# Rev_B.net
KiCad netlist of a schematic drawn in EAGLE
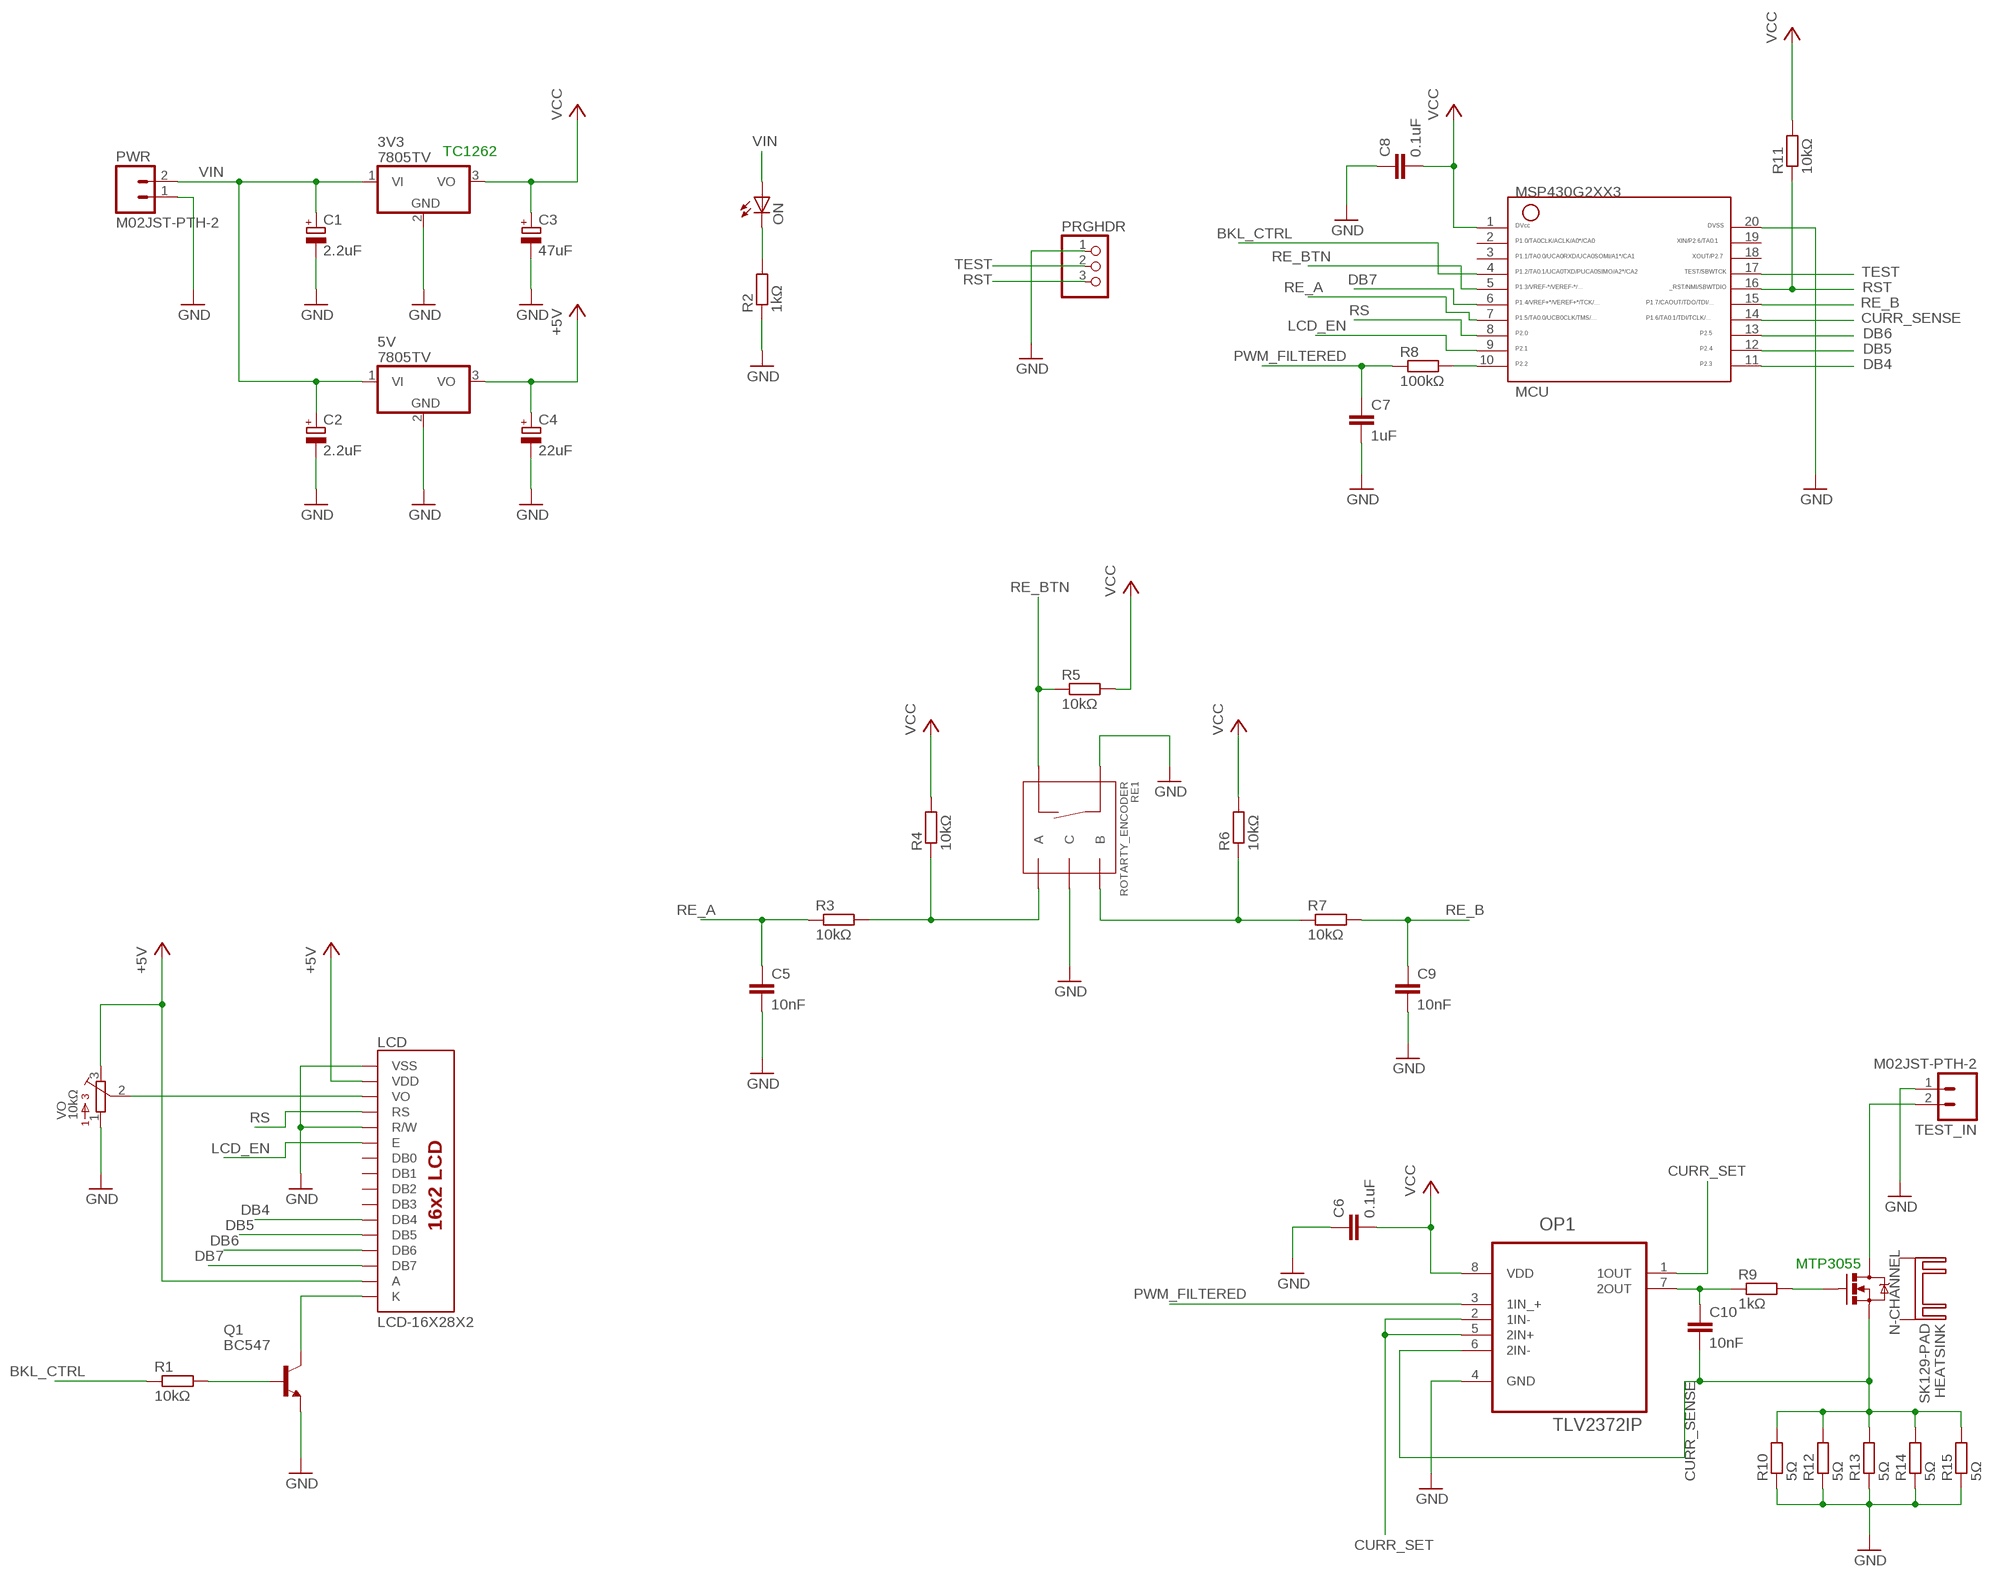
[diagram p0: schematic, sheet 1]

(export (version "E")
  (design (tool "Eeschema 10.0.6"))
  (components
    (comp (ref "3V3")
      (value "7805TV")
      (footprint "eagle-import:TO220V")
      (libsource (lib "eagle-import") (part "78TV05"))
    )
    (comp (ref "5V")
      (value "7805TV")
      (footprint "eagle-import:TO220V")
      (libsource (lib "eagle-import") (part "78TV05"))
    )
    (comp (ref "C1")
      (value "2.2uF")
      (footprint "eagle-import:E2,5-6")
      (libsource (lib "eagle-import") (part "CPOL-EUE2.5-6"))
    )
    (comp (ref "C2")
      (value "2.2uF")
      (footprint "eagle-import:E2,5-6")
      (libsource (lib "eagle-import") (part "CPOL-EUE2.5-6"))
    )
    (comp (ref "C3")
      (value "47uF")
      (footprint "eagle-import:E2,5-6")
      (libsource (lib "eagle-import") (part "CPOL-EUE2.5-6"))
    )
    (comp (ref "C4")
      (value "22uF")
      (footprint "eagle-import:E2,5-6")
      (libsource (lib "eagle-import") (part "CPOL-EUE2.5-6"))
    )
    (comp (ref "C5")
      (value "10nF")
      (footprint "eagle-import:C050-025X075")
      (libsource (lib "eagle-import") (part "C-EU050-025X075"))
    )
    (comp (ref "C6")
      (value "0.1uF")
      (footprint "eagle-import:C050-025X075")
      (libsource (lib "eagle-import") (part "C-EU050-025X075"))
    )
    (comp (ref "C7")
      (value "1uF")
      (footprint "eagle-import:C025-025X050")
      (libsource (lib "eagle-import") (part "C-EU025-025X050"))
    )
    (comp (ref "C8")
      (value "0.1uF")
      (footprint "eagle-import:C050-025X075")
      (libsource (lib "eagle-import") (part "C-EU050-025X075"))
    )
    (comp (ref "C9")
      (value "10nF")
      (footprint "eagle-import:C050-025X075")
      (libsource (lib "eagle-import") (part "C-EU050-025X075"))
    )
    (comp (ref "C10")
      (value "10nF")
      (footprint "eagle-import:C050-025X075")
      (libsource (lib "eagle-import") (part "C-EU050-025X075"))
    )
    (comp (ref "HEATSINK")
      (value "SK129-PAD")
      (footprint "eagle-import:SK129")
      (libsource (lib "eagle-import") (part "SK129-PAD"))
    )
    (comp (ref "LCD")
      (value "LCD-16X28X2")
      (footprint "eagle-import:LCD-8X2")
      (libsource (lib "eagle-import") (part "LCD-16X28X2"))
    )
    (comp (ref "MCU")
      (value "G2XX3---N20")
      (footprint "eagle-import:N20")
      (libsource (lib "eagle-import") (part "G2XX3---N20"))
    )
    (comp (ref "N-CHANNEL")
      (value "MOSFET-NCHANNELFQP30N06L")
      (footprint "eagle-import:TO220V")
      (libsource (lib "eagle-import") (part "MOSFET-NCHANNELFQP30N06L"))
    )
    (comp (ref "ON")
      (value "LEDSQR2X5")
      (footprint "eagle-import:LED2X5")
      (libsource (lib "eagle-import") (part "LEDSQR2X5"))
    )
    (comp (ref "OP1")
      (value "TLV2372IP")
      (footprint "eagle-import:DIP254P762X508-8")
      (libsource (lib "eagle-import") (part "TLV2372IP"))
    )
    (comp (ref "PRGHDR")
      (value "PINHD-1X3")
      (footprint "eagle-import:1X03")
      (libsource (lib "eagle-import") (part "PINHD-1X3"))
    )
    (comp (ref "PWR")
      (value "M02JST-PTH-2")
      (footprint "eagle-import:JST-2-PTH")
      (libsource (lib "eagle-import") (part "M02JST-PTH-2"))
    )
    (comp (ref "Q1")
      (value "BC547")
      (footprint "eagle-import:TO92")
      (libsource (lib "eagle-import") (part "BC547"))
    )
    (comp (ref "R1")
      (value "10kΩ")
      (footprint "eagle-import:0207_10")
      (libsource (lib "eagle-import") (part "resistor_R-EU_0207/10"))
    )
    (comp (ref "R2")
      (value "1kΩ")
      (footprint "eagle-import:0207_10")
      (libsource (lib "eagle-import") (part "resistor_R-EU_0207/10"))
    )
    (comp (ref "R3")
      (value "10kΩ")
      (footprint "eagle-import:0207_10")
      (libsource (lib "eagle-import") (part "resistor_R-EU_0207/10"))
    )
    (comp (ref "R4")
      (value "10kΩ")
      (footprint "eagle-import:0207_10")
      (libsource (lib "eagle-import") (part "resistor_R-EU_0207/10"))
    )
    (comp (ref "R5")
      (value "10kΩ")
      (footprint "eagle-import:0207_10")
      (libsource (lib "eagle-import") (part "resistor_R-EU_0207/10"))
    )
    (comp (ref "R6")
      (value "10kΩ")
      (footprint "eagle-import:0207_10")
      (libsource (lib "eagle-import") (part "resistor_R-EU_0207/10"))
    )
    (comp (ref "R7")
      (value "10kΩ")
      (footprint "eagle-import:0207_10")
      (libsource (lib "eagle-import") (part "resistor_R-EU_0207/10"))
    )
    (comp (ref "R8")
      (value "100kΩ")
      (footprint "eagle-import:0207_10")
      (libsource (lib "eagle-import") (part "resistor_R-EU_0207/10"))
    )
    (comp (ref "R9")
      (value "1kΩ")
      (footprint "eagle-import:0207_10")
      (libsource (lib "eagle-import") (part "resistor_R-EU_0207/10"))
    )
    (comp (ref "R10")
      (value "5Ω")
      (footprint "eagle-import:P0613_15")
      (libsource (lib "eagle-import") (part "R-EU_0613/15"))
    )
    (comp (ref "R11")
      (value "10kΩ")
      (footprint "eagle-import:0207_10")
      (libsource (lib "eagle-import") (part "resistor_R-EU_0207/10"))
    )
    (comp (ref "R12")
      (value "5Ω")
      (footprint "eagle-import:P0613_15")
      (libsource (lib "eagle-import") (part "R-EU_0613/15"))
    )
    (comp (ref "R13")
      (value "5Ω")
      (footprint "eagle-import:P0613_15")
      (libsource (lib "eagle-import") (part "R-EU_0613/15"))
    )
    (comp (ref "R14")
      (value "5Ω")
      (footprint "eagle-import:P0613_15")
      (libsource (lib "eagle-import") (part "R-EU_0613/15"))
    )
    (comp (ref "R15")
      (value "5Ω")
      (footprint "eagle-import:P0613_15")
      (libsource (lib "eagle-import") (part "R-EU_0613/15"))
    )
    (comp (ref "RE1")
      (value "ROTARTY_ENCODER")
      (footprint "eagle-import:ROTARY_ENC_PLAIN")
      (libsource (lib "eagle-import") (part "ROTARTY_ENCODER"))
    )
    (comp (ref "TEST_IN")
      (value "M02JST-PTH-2")
      (footprint "eagle-import:JST-2-PTH")
      (libsource (lib "eagle-import") (part "M02JST-PTH-2"))
    )
    (comp (ref "VO")
      (value "10kΩ")
      (footprint "eagle-import:3362H")
      (libsource (lib "eagle-import") (part "3362H"))
    )
  )
  (nets
    (net (code "1") (name "+5V") (class "Default")
      (node (ref "5V") (pin "3") (pinfunction "VO_3") (pintype "passive"))
      (node (ref "C4") (pin "+") (pinfunction "+_+") (pintype "passive"))
      (node (ref "LCD") (pin "15") (pinfunction "A_15") (pintype "power_in"))
      (node (ref "LCD") (pin "2") (pinfunction "VDD_2") (pintype "power_in"))
      (node (ref "VO") (pin "3") (pinfunction "3_3") (pintype "passive"))
    )
    (net (code "2") (name "/BKL_CTRL") (class "Default")
      (node (ref "MCU") (pin "4") (pinfunction "4_4") (pintype "bidirectional"))
      (node (ref "R1") (pin "1") (pinfunction "1_1") (pintype "passive"))
    )
    (net (code "3") (name "/CURR_SENSE") (class "Default")
      (node (ref "C10") (pin "2") (pinfunction "2_2") (pintype "passive"))
      (node (ref "MCU") (pin "14") (pinfunction "14_14") (pintype "bidirectional"))
      (node (ref "N-CHANNEL") (pin "3") (pinfunction "S_3") (pintype "passive"))
      (node (ref "OP1") (pin "6") (pinfunction "2IN-_6") (pintype "input"))
      (node (ref "R10") (pin "2") (pinfunction "2_2") (pintype "passive"))
      (node (ref "R12") (pin "2") (pinfunction "2_2") (pintype "passive"))
      (node (ref "R13") (pin "2") (pinfunction "2_2") (pintype "passive"))
      (node (ref "R14") (pin "2") (pinfunction "2_2") (pintype "passive"))
      (node (ref "R15") (pin "2") (pinfunction "2_2") (pintype "passive"))
    )
    (net (code "4") (name "/CURR_SET") (class "Default")
      (node (ref "OP1") (pin "1") (pinfunction "1OUT_1") (pintype "output"))
      (node (ref "OP1") (pin "2") (pinfunction "1IN-_2") (pintype "input"))
      (node (ref "OP1") (pin "5") (pinfunction "2IN+_5") (pintype "input"))
    )
    (net (code "5") (name "/DB4") (class "Default")
      (node (ref "LCD") (pin "11") (pinfunction "DB4_11") (pintype "bidirectional"))
      (node (ref "MCU") (pin "11") (pinfunction "11_11") (pintype "bidirectional"))
    )
    (net (code "6") (name "/DB5") (class "Default")
      (node (ref "LCD") (pin "12") (pinfunction "DB5_12") (pintype "bidirectional"))
      (node (ref "MCU") (pin "12") (pinfunction "12_12") (pintype "bidirectional"))
    )
    (net (code "7") (name "/DB6") (class "Default")
      (node (ref "LCD") (pin "13") (pinfunction "DB6_13") (pintype "bidirectional"))
      (node (ref "MCU") (pin "13") (pinfunction "13_13") (pintype "bidirectional"))
    )
    (net (code "8") (name "/DB7") (class "Default")
      (node (ref "LCD") (pin "14") (pinfunction "DB7_14") (pintype "bidirectional"))
      (node (ref "MCU") (pin "6") (pinfunction "6_6") (pintype "bidirectional"))
    )
    (net (code "9") (name "/LCD_EN") (class "Default")
      (node (ref "LCD") (pin "6") (pinfunction "E_6") (pintype "input"))
      (node (ref "MCU") (pin "9") (pinfunction "9_9") (pintype "bidirectional"))
    )
    (net (code "10") (name "/PWM_FILTERED") (class "Default")
      (node (ref "C7") (pin "1") (pinfunction "1_1") (pintype "passive"))
      (node (ref "OP1") (pin "3") (pinfunction "1IN_+_3") (pintype "input"))
      (node (ref "R8") (pin "1") (pinfunction "1_1") (pintype "passive"))
    )
    (net (code "11") (name "/RE_A") (class "Default")
      (node (ref "C5") (pin "1") (pinfunction "1_1") (pintype "passive"))
      (node (ref "MCU") (pin "7") (pinfunction "7_7") (pintype "bidirectional"))
      (node (ref "R3") (pin "1") (pinfunction "1_1") (pintype "passive"))
    )
    (net (code "12") (name "/RE_B") (class "Default")
      (node (ref "C9") (pin "1") (pinfunction "1_1") (pintype "passive"))
      (node (ref "MCU") (pin "15") (pinfunction "15_15") (pintype "bidirectional"))
      (node (ref "R7") (pin "2") (pinfunction "2_2") (pintype "passive"))
    )
    (net (code "13") (name "/RE_BTN") (class "Default")
      (node (ref "MCU") (pin "5") (pinfunction "5_5") (pintype "bidirectional"))
      (node (ref "R5") (pin "1") (pinfunction "1_1") (pintype "passive"))
      (node (ref "RE1") (pin "SW-") (pinfunction "SW-_SW-") (pintype "bidirectional"))
    )
    (net (code "14") (name "/RS") (class "Default")
      (node (ref "LCD") (pin "4") (pinfunction "RS_4") (pintype "input"))
      (node (ref "MCU") (pin "8") (pinfunction "8_8") (pintype "bidirectional"))
    )
    (net (code "15") (name "/RST") (class "Default")
      (node (ref "MCU") (pin "16") (pinfunction "16_16") (pintype "bidirectional"))
      (node (ref "PRGHDR") (pin "3") (pinfunction "3_3") (pintype "passive"))
      (node (ref "R11") (pin "1") (pinfunction "1_1") (pintype "passive"))
    )
    (net (code "16") (name "/TEST") (class "Default")
      (node (ref "MCU") (pin "17") (pinfunction "17_17") (pintype "bidirectional"))
      (node (ref "PRGHDR") (pin "2") (pinfunction "2_2") (pintype "passive"))
    )
    (net (code "17") (name "/VIN") (class "Default")
      (node (ref "3V3") (pin "1") (pinfunction "VI_1") (pintype "input"))
      (node (ref "5V") (pin "1") (pinfunction "VI_1") (pintype "input"))
      (node (ref "C1") (pin "+") (pinfunction "+_+") (pintype "passive"))
      (node (ref "C2") (pin "+") (pinfunction "+_+") (pintype "passive"))
      (node (ref "ON") (pin "A") (pinfunction "A_A") (pintype "passive"))
      (node (ref "PWR") (pin "2") (pinfunction "2_2") (pintype "passive"))
    )
    (net (code "18") (name "GND") (class "Default")
      (node (ref "3V3") (pin "2") (pinfunction "GND_2") (pintype "passive"))
      (node (ref "5V") (pin "2") (pinfunction "GND_2") (pintype "passive"))
      (node (ref "C1") (pin "-") (pinfunction "-_-") (pintype "passive"))
      (node (ref "C2") (pin "-") (pinfunction "-_-") (pintype "passive"))
      (node (ref "C3") (pin "-") (pinfunction "-_-") (pintype "passive"))
      (node (ref "C4") (pin "-") (pinfunction "-_-") (pintype "passive"))
      (node (ref "C5") (pin "2") (pinfunction "2_2") (pintype "passive"))
      (node (ref "C6") (pin "1") (pinfunction "1_1") (pintype "passive"))
      (node (ref "C7") (pin "2") (pinfunction "2_2") (pintype "passive"))
      (node (ref "C8") (pin "1") (pinfunction "1_1") (pintype "passive"))
      (node (ref "C9") (pin "2") (pinfunction "2_2") (pintype "passive"))
      (node (ref "LCD") (pin "1") (pinfunction "VSS_1") (pintype "power_in"))
      (node (ref "LCD") (pin "5") (pinfunction "R/W_5") (pintype "input"))
      (node (ref "MCU") (pin "20") (pinfunction "20_20") (pintype "bidirectional"))
      (node (ref "OP1") (pin "4") (pinfunction "GND_4") (pintype "passive"))
      (node (ref "PRGHDR") (pin "1") (pinfunction "1_1") (pintype "passive"))
      (node (ref "PWR") (pin "1") (pinfunction "1_1") (pintype "passive"))
      (node (ref "Q1") (pin "1") (pinfunction "E_1") (pintype "passive"))
      (node (ref "R10") (pin "1") (pinfunction "1_1") (pintype "passive"))
      (node (ref "R12") (pin "1") (pinfunction "1_1") (pintype "passive"))
      (node (ref "R13") (pin "1") (pinfunction "1_1") (pintype "passive"))
      (node (ref "R14") (pin "1") (pinfunction "1_1") (pintype "passive"))
      (node (ref "R15") (pin "1") (pinfunction "1_1") (pintype "passive"))
      (node (ref "R2") (pin "1") (pinfunction "1_1") (pintype "passive"))
      (node (ref "RE1") (pin "C") (pinfunction "C_C") (pintype "bidirectional"))
      (node (ref "RE1") (pin "SW+") (pinfunction "SW+_SW+") (pintype "bidirectional"))
      (node (ref "TEST_IN") (pin "1") (pinfunction "1_1") (pintype "passive"))
      (node (ref "VO") (pin "1") (pinfunction "1_1") (pintype "passive"))
    )
    (net (code "19") (name "Net-(LCD-K)") (class "Default")
      (node (ref "LCD") (pin "16") (pinfunction "K_16") (pintype "power_in"))
      (node (ref "Q1") (pin "3") (pinfunction "C_3") (pintype "passive"))
    )
    (net (code "20") (name "Net-(LCD-VO)") (class "Default")
      (node (ref "LCD") (pin "3") (pinfunction "VO_3") (pintype "bidirectional"))
      (node (ref "VO") (pin "2") (pinfunction "2_2") (pintype "passive"))
    )
    (net (code "21") (name "Net-(MCU-Pad10)") (class "Default")
      (node (ref "MCU") (pin "10") (pinfunction "10_10") (pintype "bidirectional"))
      (node (ref "R8") (pin "2") (pinfunction "2_2") (pintype "passive"))
    )
    (net (code "22") (name "Net-(N-CHANNEL-D)") (class "Default")
      (node (ref "N-CHANNEL") (pin "2") (pinfunction "D_2") (pintype "passive"))
      (node (ref "TEST_IN") (pin "2") (pinfunction "2_2") (pintype "passive"))
    )
    (net (code "23") (name "Net-(N-CHANNEL-G)") (class "Default")
      (node (ref "N-CHANNEL") (pin "1") (pinfunction "G_1") (pintype "passive"))
      (node (ref "R9") (pin "2") (pinfunction "2_2") (pintype "passive"))
    )
    (net (code "24") (name "Net-(ON-C)") (class "Default")
      (node (ref "ON") (pin "K") (pinfunction "C_K") (pintype "passive"))
      (node (ref "R2") (pin "2") (pinfunction "2_2") (pintype "passive"))
    )
    (net (code "25") (name "Net-(OP1-2OUT)") (class "Default")
      (node (ref "C10") (pin "1") (pinfunction "1_1") (pintype "passive"))
      (node (ref "OP1") (pin "7") (pinfunction "2OUT_7") (pintype "output"))
      (node (ref "R9") (pin "1") (pinfunction "1_1") (pintype "passive"))
    )
    (net (code "26") (name "Net-(Q1-B)") (class "Default")
      (node (ref "Q1") (pin "2") (pinfunction "B_2") (pintype "passive"))
      (node (ref "R1") (pin "2") (pinfunction "2_2") (pintype "passive"))
    )
    (net (code "27") (name "Net-(R3-Pad2)") (class "Default")
      (node (ref "R3") (pin "2") (pinfunction "2_2") (pintype "passive"))
      (node (ref "R4") (pin "1") (pinfunction "1_1") (pintype "passive"))
      (node (ref "RE1") (pin "A") (pinfunction "A_A") (pintype "bidirectional"))
    )
    (net (code "28") (name "Net-(R6-Pad1)") (class "Default")
      (node (ref "R6") (pin "1") (pinfunction "1_1") (pintype "passive"))
      (node (ref "R7") (pin "1") (pinfunction "1_1") (pintype "passive"))
      (node (ref "RE1") (pin "B") (pinfunction "B_B") (pintype "bidirectional"))
    )
    (net (code "29") (name "VCC") (class "Default")
      (node (ref "3V3") (pin "3") (pinfunction "VO_3") (pintype "passive"))
      (node (ref "C3") (pin "+") (pinfunction "+_+") (pintype "passive"))
      (node (ref "C6") (pin "2") (pinfunction "2_2") (pintype "passive"))
      (node (ref "C8") (pin "2") (pinfunction "2_2") (pintype "passive"))
      (node (ref "MCU") (pin "1") (pinfunction "1_1") (pintype "bidirectional"))
      (node (ref "OP1") (pin "8") (pinfunction "VDD_8") (pintype "power_in"))
      (node (ref "R11") (pin "2") (pinfunction "2_2") (pintype "passive"))
      (node (ref "R4") (pin "2") (pinfunction "2_2") (pintype "passive"))
      (node (ref "R5") (pin "2") (pinfunction "2_2") (pintype "passive"))
      (node (ref "R6") (pin "2") (pinfunction "2_2") (pintype "passive"))
    )
    (net (code "30") (name "unconnected-(HEATSINK-K-PadA2,5)") (class "Default")
      (node (ref "HEATSINK") (pin "A2,5") (pinfunction "K_A2,5") (pintype "passive"))
    )
    (net (code "31") (name "unconnected-(HEATSINK-K-PadB2,5)") (class "Default")
      (node (ref "HEATSINK") (pin "B2,5") (pinfunction "K_B2,5") (pintype "passive"))
    )
    (net (code "32") (name "unconnected-(LCD-DB0-Pad7)") (class "Default")
      (node (ref "LCD") (pin "7") (pinfunction "DB0_7") (pintype "bidirectional"))
    )
    (net (code "33") (name "unconnected-(LCD-DB1-Pad8)") (class "Default")
      (node (ref "LCD") (pin "8") (pinfunction "DB1_8") (pintype "bidirectional"))
    )
    (net (code "34") (name "unconnected-(LCD-DB2-Pad9)") (class "Default")
      (node (ref "LCD") (pin "9") (pinfunction "DB2_9") (pintype "bidirectional"))
    )
    (net (code "35") (name "unconnected-(LCD-DB3-Pad10)") (class "Default")
      (node (ref "LCD") (pin "10") (pinfunction "DB3_10") (pintype "bidirectional"))
    )
    (net (code "36") (name "unconnected-(MCU-Pad2)") (class "Default")
      (node (ref "MCU") (pin "2") (pinfunction "2_2") (pintype "bidirectional"))
    )
    (net (code "37") (name "unconnected-(MCU-Pad3)") (class "Default")
      (node (ref "MCU") (pin "3") (pinfunction "3_3") (pintype "bidirectional"))
    )
    (net (code "38") (name "unconnected-(MCU-Pad18)") (class "Default")
      (node (ref "MCU") (pin "18") (pinfunction "18_18") (pintype "bidirectional"))
    )
    (net (code "39") (name "unconnected-(MCU-Pad19)") (class "Default")
      (node (ref "MCU") (pin "19") (pinfunction "19_19") (pintype "bidirectional"))
    )
  )
)
